# AWR2243_DUT.net
KiCad netlist of a schematic drawn in Altium Designer
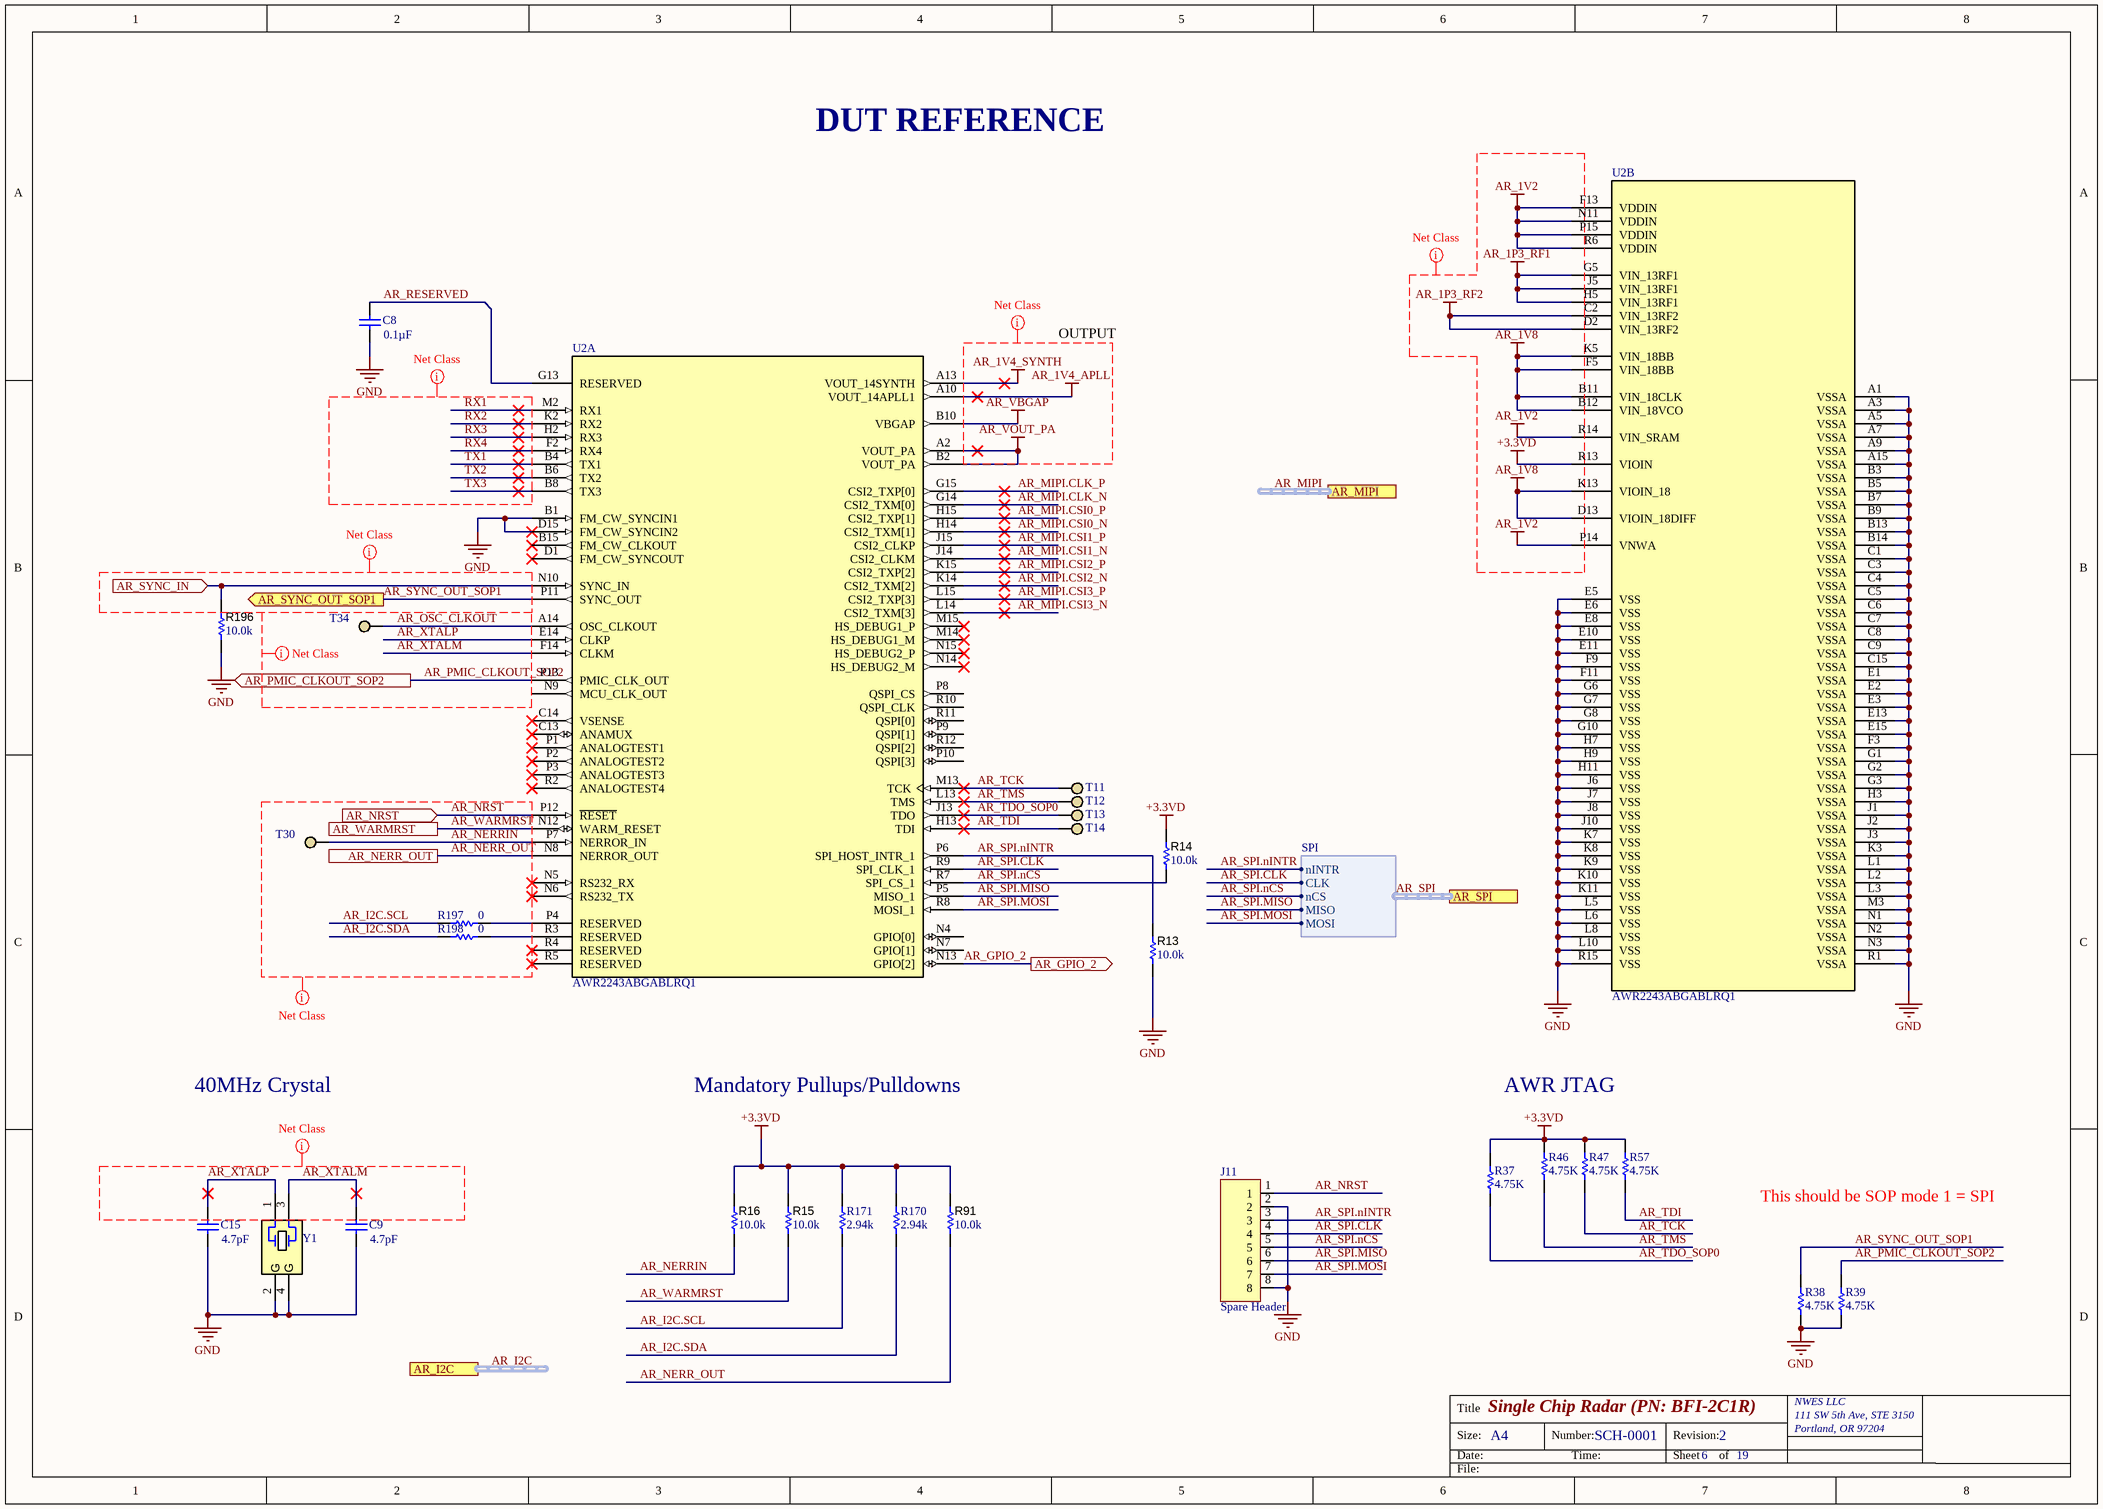
[diagram p0: AWR2243_DUT.SchDoc]

(export (version "E")
  (design (tool "Eeschema 10.0.6"))
  (components
    (comp (ref "C8")
      (value "C0603X7S1A104K030BC")
      (footprint "0201_033")
      (description "CAP, CERM, 0.1 µF, 10 V,+/- 10%, X7S, 0201")
      (fields (field (name "MANUFACTURER") "TDK") (field (name "VALUEDISPLAYED") "0.1µF"))
      (libsource (lib "Altium Vault - TI") (part "Capacitor"))
    )
    (comp (ref "C9")
      (value "GJM1555C1H4R7BB01D")
      (footprint "0402")
      (description "CAP, CERM, 4.7 pF, 50 V, +/- 2%, C0G/NP0, 0402")
      (fields
        (field (name "MANUFACTURER") "MuRata")
        (field (name "VALUEDISPLAYED") "4.7pF")
        (field (name "PUBLISHER") "Texas Instruments")
      )
      (libsource (lib "Altium Vault - TI") (part "CMP-0006367-2"))
    )
    (comp (ref "C15")
      (value "GJM1555C1H4R7BB01D")
      (footprint "0402")
      (description "CAP, CERM, 4.7 pF, 50 V, +/- 2%, C0G/NP0, 0402")
      (fields
        (field (name "MANUFACTURER") "MuRata")
        (field (name "VALUEDISPLAYED") "4.7pF")
        (field (name "PUBLISHER") "Texas Instruments")
      )
      (libsource (lib "Altium Vault - TI") (part "CMP-0006367-2"))
    )
    (comp (ref "J11")
      (value "Spare Header")
      (footprint "HDR8X1_2.54MM")
      (description "Conn Header Vert 8POS 2.54MM")
      (fields
        (field (name "MANUFACTURER") "Sullins")
        (field (name "MANUFACTURER PART NUMBER") "PREC008SAAN-RC")
      )
      (libsource (lib "Radar FPGA RF") (part "Header 8X1"))
    )
    (comp (ref "R13")
      (value "CRCW040210K0FKED")
      (footprint "0402L")
      (description "RES, 10.0 k, 1%, 0.063 W, AEC-Q200 Grade 0, 0402")
      (fields (field (name "MANUFACTURER") "Vishay-Dale") (field (name "VALUEDISPLAYED") "10.0k"))
      (libsource (lib "Altium Vault - TI") (part "Resistor"))
    )
    (comp (ref "R14")
      (value "CRCW040210K0FKED")
      (footprint "0402L")
      (description "RES, 10.0 k, 1%, 0.063 W, AEC-Q200 Grade 0, 0402")
      (fields (field (name "MANUFACTURER") "Vishay-Dale") (field (name "VALUEDISPLAYED") "10.0k"))
      (libsource (lib "Altium Vault - TI") (part "Resistor"))
    )
    (comp (ref "R15")
      (value "CRCW040210K0FKED")
      (footprint "0402L")
      (description "RES, 10.0 k, 1%, 0.063 W, AEC-Q200 Grade 0, 0402")
      (fields (field (name "MANUFACTURER") "Vishay-Dale") (field (name "VALUEDISPLAYED") "10.0k"))
      (libsource (lib "Altium Vault - TI") (part "Resistor"))
    )
    (comp (ref "R16")
      (value "CRCW040210K0FKED")
      (footprint "0402L")
      (description "RES, 10.0 k, 1%, 0.063 W, AEC-Q200 Grade 0, 0402")
      (fields (field (name "MANUFACTURER") "Vishay-Dale") (field (name "VALUEDISPLAYED") "10.0k"))
      (libsource (lib "Altium Vault - TI") (part "Resistor"))
    )
    (comp (ref "R37")
      (value "4.75K")
      (footprint "RESC1005X40USR")
      (description "RES 4.75K OHM 1% 1/16W 0402")
      (fields
        (field (name "MANUFACTURER") "YAGEO")
        (field (name "MANUFACTURER PART NUMBER") "RC0402FR-074K75L")
      )
      (libsource (lib "Radar FPGA RF") (part "RES 4.75K OHM 1% 1/16W 0402"))
    )
    (comp (ref "R38")
      (value "4.75K")
      (footprint "RESC1005X40USR")
      (description "RES 4.75K OHM 1% 1/16W 0402")
      (fields
        (field (name "MANUFACTURER") "YAGEO")
        (field (name "MANUFACTURER PART NUMBER") "RC0402FR-074K75L")
      )
      (libsource (lib "Radar FPGA RF") (part "RES 4.75K OHM 1% 1/16W 0402"))
    )
    (comp (ref "R39")
      (value "4.75K")
      (footprint "RESC1005X40USR")
      (description "RES 4.75K OHM 1% 1/16W 0402")
      (fields
        (field (name "MANUFACTURER") "YAGEO")
        (field (name "MANUFACTURER PART NUMBER") "RC0402FR-074K75L")
      )
      (libsource (lib "Radar FPGA RF") (part "RES 4.75K OHM 1% 1/16W 0402"))
    )
    (comp (ref "R46")
      (value "4.75K")
      (footprint "RESC1005X40USR")
      (description "RES 4.75K OHM 1% 1/16W 0402")
      (fields
        (field (name "MANUFACTURER") "YAGEO")
        (field (name "MANUFACTURER PART NUMBER") "RC0402FR-074K75L")
      )
      (libsource (lib "Radar FPGA RF") (part "RES 4.75K OHM 1% 1/16W 0402"))
    )
    (comp (ref "R47")
      (value "4.75K")
      (footprint "RESC1005X40USR")
      (description "RES 4.75K OHM 1% 1/16W 0402")
      (fields
        (field (name "MANUFACTURER") "YAGEO")
        (field (name "MANUFACTURER PART NUMBER") "RC0402FR-074K75L")
      )
      (libsource (lib "Radar FPGA RF") (part "RES 4.75K OHM 1% 1/16W 0402"))
    )
    (comp (ref "R57")
      (value "4.75K")
      (footprint "RESC1005X40USR")
      (description "RES 4.75K OHM 1% 1/16W 0402")
      (fields
        (field (name "MANUFACTURER") "YAGEO")
        (field (name "MANUFACTURER PART NUMBER") "RC0402FR-074K75L")
      )
      (libsource (lib "Radar FPGA RF") (part "RES 4.75K OHM 1% 1/16W 0402"))
    )
    (comp (ref "R91")
      (value "CRCW040210K0FKED")
      (footprint "0402L")
      (description "RES, 10.0 k, 1%, 0.063 W, AEC-Q200 Grade 0, 0402")
      (fields (field (name "MANUFACTURER") "Vishay-Dale") (field (name "VALUEDISPLAYED") "10.0k"))
      (libsource (lib "Altium Vault - TI") (part "Resistor"))
    )
    (comp (ref "R170")
      (value "CRCW04022K94FKED")
      (footprint "0402")
      (description "RES, 2.94 k, 1%, 0.063 W, AEC-Q200 Grade 0, 0402")
      (fields (field (name "MANUFACTURER") "Vishay-Dale") (field (name "VALUEDISPLAYED") "2.94k"))
      (libsource (lib "Altium Vault - TI") (part "Resistor"))
    )
    (comp (ref "R171")
      (value "CRCW04022K94FKED")
      (footprint "0402")
      (description "RES, 2.94 k, 1%, 0.063 W, AEC-Q200 Grade 0, 0402")
      (fields (field (name "MANUFACTURER") "Vishay-Dale") (field (name "VALUEDISPLAYED") "2.94k"))
      (libsource (lib "Altium Vault - TI") (part "Resistor"))
    )
    (comp (ref "R196")
      (value "CRCW040210K0FKED")
      (footprint "0402L")
      (description "RES, 10.0 k, 1%, 0.063 W, AEC-Q200 Grade 0, 0402")
      (fields (field (name "MANUFACTURER") "Vishay-Dale") (field (name "VALUEDISPLAYED") "10.0k"))
      (libsource (lib "Altium Vault - TI") (part "CMP-0025958-3"))
    )
    (comp (ref "R197")
      (value "CRCW02010000Z0ED")
      (footprint "0201")
      (description "RES, 0, 5%, 0.05 W, 0201")
      (fields (field (name "MANUFACTURER") "Vishay-Dale") (field (name "VALUEDISPLAYED") "0"))
      (libsource (lib "Altium Vault - TI") (part "Resistor"))
    )
    (comp (ref "R198")
      (value "CRCW02010000Z0ED")
      (footprint "0201")
      (description "RES, 0, 5%, 0.05 W, 0201")
      (fields (field (name "MANUFACTURER") "Vishay-Dale") (field (name "VALUEDISPLAYED") "0"))
      (libsource (lib "Altium Vault - TI") (part "Resistor"))
    )
    (comp (ref "T11")
      (value "TP_S")
      (footprint "TP_SM_1MM")
      (description "test point")
      (libsource (lib "Radar FPGA RF") (part "Test point PAD"))
    )
    (comp (ref "T12")
      (value "TP_S")
      (footprint "TP_SM_1MM")
      (description "test point")
      (libsource (lib "Radar FPGA RF") (part "Test point PAD"))
    )
    (comp (ref "T13")
      (value "TP_S")
      (footprint "TP_SM_1MM")
      (description "test point")
      (libsource (lib "Radar FPGA RF") (part "Test point PAD"))
    )
    (comp (ref "T14")
      (value "TP_S")
      (footprint "TP_SM_1MM")
      (description "test point")
      (libsource (lib "Radar FPGA RF") (part "Test point PAD"))
    )
    (comp (ref "T30")
      (value "TP_S")
      (footprint "TP_SM_1MM")
      (description "test point")
      (libsource (lib "Radar FPGA RF") (part "Test point PAD"))
    )
    (comp (ref "T34")
      (value "TP_S")
      (footprint "TP_SM_1MM")
      (description "test point")
      (libsource (lib "Radar FPGA RF") (part "Test point PAD"))
    )
    (comp (ref "U2")
      (value "AWR2243APBGABLQ1")
      (footprint "ABL0161A")
      (description "Single Chip 77 and 79 GHz FMCW Transceiver, ABL0161A (FCBGA-161)")
      (fields
        (field (name "ALTERNATE PARTNUMBER") "AWR2243ABGABLRQ1")
        (field (name "MANUFACTURER") "Texas Instruments")
        (field (name "PARTNUMBER") "AWR2243ABGABLRQ1")
      )
      (libsource (lib "Altium Vault - TI") (part "CMP-0081285-1"))
    )
    (comp (ref "Y1")
      (value "CX3225SA40000D0PTWCC")
      (footprint "Kyocera_CX3225SA")
      (description "Crystal, 40 MHz, 8pF, SMD")
      (fields (field (name "MANUFACTURER") "Kyocera"))
      (libsource (lib "Altium Vault - TI") (part "XTAL_4P_13_24OPEN"))
    )
  )
  (nets
    (net (code "4") (name "+3.3VD") (class "Default")
      (node (ref "R14") (pin "2") (pinfunction "2_2") (pintype "passive"))
      (node (ref "R15") (pin "2") (pinfunction "2_2") (pintype "passive"))
      (node (ref "R16") (pin "2") (pinfunction "2_2") (pintype "passive"))
      (node (ref "R170") (pin "2") (pinfunction "2_2") (pintype "passive"))
      (node (ref "R171") (pin "2") (pinfunction "2_2") (pintype "passive"))
      (node (ref "R37") (pin "2") (pinfunction "2_2") (pintype "passive"))
      (node (ref "R46") (pin "2") (pinfunction "2_2") (pintype "passive"))
      (node (ref "R47") (pin "2") (pinfunction "2_2") (pintype "passive"))
      (node (ref "R57") (pin "2") (pinfunction "2_2") (pintype "passive"))
      (node (ref "R91") (pin "2") (pinfunction "2_2") (pintype "passive"))
      (node (ref "U2") (pin "R13") (pinfunction "VIOIN_R13") (pintype "power_in"))
    )
    (net (code "5") (name "/AR_GPIO_2") (class "Default")
      (node (ref "U2") (pin "N13") (pinfunction "GPIO[2]_N13") (pintype "bidirectional"))
    )
    (net (code "6") (name "/AR_I2C.SCL") (class "Default")
      (node (ref "R171") (pin "1") (pinfunction "1_1") (pintype "passive"))
      (node (ref "R197") (pin "1") (pinfunction "1_1") (pintype "passive"))
    )
    (net (code "7") (name "/AR_I2C.SDA") (class "Default")
      (node (ref "R170") (pin "1") (pinfunction "1_1") (pintype "passive"))
      (node (ref "R198") (pin "1") (pinfunction "1_1") (pintype "passive"))
    )
    (net (code "8") (name "/AR_MIPI.CLK_N") (class "Default")
      (node (ref "U2") (pin "G14") (pinfunction "CSI2_TXM[0]_G14") (pintype "output"))
    )
    (net (code "9") (name "/AR_MIPI.CLK_P") (class "Default")
      (node (ref "U2") (pin "G15") (pinfunction "CSI2_TXP[0]_G15") (pintype "output"))
    )
    (net (code "10") (name "/AR_MIPI.CSI0_N") (class "Default")
      (node (ref "U2") (pin "H14") (pinfunction "CSI2_TXM[1]_H14") (pintype "output"))
    )
    (net (code "11") (name "/AR_MIPI.CSI0_P") (class "Default")
      (node (ref "U2") (pin "H15") (pinfunction "CSI2_TXP[1]_H15") (pintype "output"))
    )
    (net (code "12") (name "/AR_MIPI.CSI1_N") (class "Default")
      (node (ref "U2") (pin "J14") (pinfunction "CSI2_CLKM_J14") (pintype "output"))
    )
    (net (code "13") (name "/AR_MIPI.CSI1_P") (class "Default")
      (node (ref "U2") (pin "J15") (pinfunction "CSI2_CLKP_J15") (pintype "output"))
    )
    (net (code "14") (name "/AR_MIPI.CSI2_N") (class "Default")
      (node (ref "U2") (pin "K14") (pinfunction "CSI2_TXM[2]_K14") (pintype "output"))
    )
    (net (code "15") (name "/AR_MIPI.CSI2_P") (class "Default")
      (node (ref "U2") (pin "K15") (pinfunction "CSI2_TXP[2]_K15") (pintype "output"))
    )
    (net (code "16") (name "/AR_MIPI.CSI3_N") (class "Default")
      (node (ref "U2") (pin "L14") (pinfunction "CSI2_TXM[3]_L14") (pintype "output"))
    )
    (net (code "17") (name "/AR_MIPI.CSI3_P") (class "Default")
      (node (ref "U2") (pin "L15") (pinfunction "CSI2_TXP[3]_L15") (pintype "output"))
    )
    (net (code "18") (name "/AR_NERRIN") (class "Default")
      (node (ref "R16") (pin "1") (pinfunction "1_1") (pintype "passive"))
      (node (ref "T30") (pin "1") (pintype "passive"))
      (node (ref "U2") (pin "P7") (pinfunction "NERROR_IN_P7") (pintype "input"))
    )
    (net (code "19") (name "/AR_NERR_OUT") (class "Default")
      (node (ref "R91") (pin "1") (pinfunction "1_1") (pintype "passive"))
      (node (ref "U2") (pin "N8") (pinfunction "NERROR_OUT_N8") (pintype "open_collector"))
    )
    (net (code "20") (name "/AR_NRST") (class "Default")
      (node (ref "J11") (pin "1") (pinfunction "1_1") (pintype "passive"))
      (node (ref "U2") (pin "P12") (pinfunction "RESET_P12") (pintype "input"))
    )
    (net (code "21") (name "/AR_OSC_CLKOUT") (class "Default")
      (node (ref "T34") (pin "1") (pintype "passive"))
      (node (ref "U2") (pin "A14") (pinfunction "OSC_CLKOUT_A14") (pintype "output"))
    )
    (net (code "22") (name "/AR_PMIC_CLKOUT_SOP2") (class "Default")
      (node (ref "R39") (pin "2") (pinfunction "2_2") (pintype "passive"))
      (node (ref "U2") (pin "P13") (pinfunction "PMIC_CLK_OUT_P13") (pintype "output"))
    )
    (net (code "23") (name "/AR_RESERVED") (class "Default")
      (node (ref "C8") (pin "1") (pinfunction "1_1") (pintype "passive"))
      (node (ref "U2") (pin "G13") (pinfunction "RESERVED_G13") (pintype "power_in"))
    )
    (net (code "24") (name "/AR_SPI.CLK") (class "Default")
      (node (ref "J11") (pin "4") (pinfunction "4_4") (pintype "passive"))
      (node (ref "U2") (pin "R9") (pinfunction "SPI_CLK_1_R9") (pintype "input"))
    )
    (net (code "25") (name "/AR_SPI.MISO") (class "Default")
      (node (ref "J11") (pin "6") (pinfunction "6_6") (pintype "passive"))
      (node (ref "U2") (pin "P5") (pinfunction "MISO_1_P5") (pintype "output"))
    )
    (net (code "26") (name "/AR_SPI.MOSI") (class "Default")
      (node (ref "J11") (pin "7") (pinfunction "7_7") (pintype "passive"))
      (node (ref "U2") (pin "R8") (pinfunction "MOSI_1_R8") (pintype "input"))
    )
    (net (code "27") (name "/AR_SPI.nCS") (class "Default")
      (node (ref "J11") (pin "5") (pinfunction "5_5") (pintype "passive"))
      (node (ref "R14") (pin "1") (pinfunction "1_1") (pintype "passive"))
      (node (ref "U2") (pin "R7") (pinfunction "SPI_CS_1_R7") (pintype "input"))
    )
    (net (code "28") (name "/AR_SPI.nINTR") (class "Default")
      (node (ref "J11") (pin "3") (pinfunction "3_3") (pintype "passive"))
      (node (ref "R13") (pin "2") (pinfunction "2_2") (pintype "passive"))
      (node (ref "U2") (pin "P6") (pinfunction "SPI_HOST_INTR_1_P6") (pintype "output"))
    )
    (net (code "30") (name "/AR_SYNC_IN") (class "Default")
      (node (ref "R196") (pin "2") (pinfunction "2_2") (pintype "passive"))
      (node (ref "U2") (pin "N10") (pinfunction "SYNC_IN_N10") (pintype "input"))
    )
    (net (code "31") (name "/AR_SYNC_OUT_SOP1") (class "Default")
      (node (ref "R38") (pin "2") (pinfunction "2_2") (pintype "passive"))
      (node (ref "U2") (pin "P11") (pinfunction "SYNC_OUT_P11") (pintype "output"))
    )
    (net (code "32") (name "/AR_TCK") (class "Default")
      (node (ref "R47") (pin "1") (pinfunction "1_1") (pintype "passive"))
      (node (ref "T11") (pin "1") (pintype "passive"))
      (node (ref "U2") (pin "M13") (pinfunction "TCK_M13") (pintype "input"))
    )
    (net (code "33") (name "/AR_TDI") (class "Default")
      (node (ref "R57") (pin "1") (pinfunction "1_1") (pintype "passive"))
      (node (ref "T14") (pin "1") (pintype "passive"))
      (node (ref "U2") (pin "H13") (pinfunction "TDI_H13") (pintype "input"))
    )
    (net (code "34") (name "/AR_TDO_SOP0") (class "Default")
      (node (ref "R37") (pin "1") (pinfunction "1_1") (pintype "passive"))
      (node (ref "T13") (pin "1") (pintype "passive"))
      (node (ref "U2") (pin "J13") (pinfunction "TDO_J13") (pintype "output"))
    )
    (net (code "35") (name "/AR_TMS") (class "Default")
      (node (ref "R46") (pin "1") (pinfunction "1_1") (pintype "passive"))
      (node (ref "T12") (pin "1") (pintype "passive"))
      (node (ref "U2") (pin "L13") (pinfunction "TMS_L13") (pintype "input"))
    )
    (net (code "36") (name "/AR_WARMRST") (class "Default")
      (node (ref "R15") (pin "1") (pinfunction "1_1") (pintype "passive"))
      (node (ref "U2") (pin "N12") (pinfunction "WARM_RESET_N12") (pintype "bidirectional"))
    )
    (net (code "37") (name "/AR_XTALM") (class "Default")
      (node (ref "C9") (pin "1") (pinfunction "1_1") (pintype "passive"))
      (node (ref "U2") (pin "F14") (pinfunction "CLKM_F14") (pintype "input"))
      (node (ref "Y1") (pin "3") (pinfunction "3_3") (pintype "passive"))
    )
    (net (code "38") (name "/AR_XTALP") (class "Default")
      (node (ref "C15") (pin "2") (pinfunction "2_2") (pintype "passive"))
      (node (ref "U2") (pin "E14") (pinfunction "CLKP_E14") (pintype "input"))
      (node (ref "Y1") (pin "1") (pinfunction "1_1") (pintype "passive"))
    )
    (net (code "39") (name "/RX1") (class "Default")
      (node (ref "U2") (pin "M2") (pinfunction "RX1_M2") (pintype "input"))
    )
    (net (code "40") (name "/RX2") (class "Default")
      (node (ref "U2") (pin "K2") (pinfunction "RX2_K2") (pintype "input"))
    )
    (net (code "41") (name "/RX3") (class "Default")
      (node (ref "U2") (pin "H2") (pinfunction "RX3_H2") (pintype "input"))
    )
    (net (code "42") (name "/RX4") (class "Default")
      (node (ref "U2") (pin "F2") (pinfunction "RX4_F2") (pintype "input"))
    )
    (net (code "43") (name "/TX1") (class "Default")
      (node (ref "U2") (pin "B4") (pinfunction "TX1_B4") (pintype "output"))
    )
    (net (code "44") (name "/TX2") (class "Default")
      (node (ref "U2") (pin "B6") (pinfunction "TX2_B6") (pintype "output"))
    )
    (net (code "45") (name "/TX3") (class "Default")
      (node (ref "U2") (pin "B8") (pinfunction "TX3_B8") (pintype "output"))
    )
    (net (code "48") (name "AR_1P3_RF1") (class "Default")
      (node (ref "U2") (pin "G5") (pinfunction "VIN_13RF1_G5") (pintype "power_in"))
      (node (ref "U2") (pin "H5") (pinfunction "VIN_13RF1_H5") (pintype "power_in"))
      (node (ref "U2") (pin "J5") (pinfunction "VIN_13RF1_J5") (pintype "power_in"))
    )
    (net (code "49") (name "AR_1P3_RF2") (class "Default")
      (node (ref "U2") (pin "C2") (pinfunction "VIN_13RF2_C2") (pintype "power_in"))
      (node (ref "U2") (pin "D2") (pinfunction "VIN_13RF2_D2") (pintype "power_in"))
    )
    (net (code "50") (name "AR_1V2") (class "Default")
      (node (ref "U2") (pin "F13") (pinfunction "VDDIN_F13") (pintype "power_in"))
      (node (ref "U2") (pin "N11") (pinfunction "VDDIN_N11") (pintype "power_in"))
      (node (ref "U2") (pin "P14") (pinfunction "VNWA_P14") (pintype "power_in"))
      (node (ref "U2") (pin "P15") (pinfunction "VDDIN_P15") (pintype "power_in"))
      (node (ref "U2") (pin "R14") (pinfunction "VIN_SRAM_R14") (pintype "power_in"))
      (node (ref "U2") (pin "R6") (pinfunction "VDDIN_R6") (pintype "power_in"))
    )
    (net (code "51") (name "AR_1V4_APLL") (class "Default")
      (node (ref "U2") (pin "A10") (pinfunction "VOUT_14APLL1_A10") (pintype "output"))
    )
    (net (code "52") (name "AR_1V4_SYNTH") (class "Default")
      (node (ref "U2") (pin "A13") (pinfunction "VOUT_14SYNTH_A13") (pintype "output"))
    )
    (net (code "53") (name "AR_1V8") (class "Default")
      (node (ref "U2") (pin "B11") (pinfunction "VIN_18CLK_B11") (pintype "power_in"))
      (node (ref "U2") (pin "B12") (pinfunction "VIN_18VCO_B12") (pintype "power_in"))
      (node (ref "U2") (pin "D13") (pinfunction "VIOIN_18DIFF_D13") (pintype "power_in"))
      (node (ref "U2") (pin "F5") (pinfunction "VIN_18BB_F5") (pintype "power_in"))
      (node (ref "U2") (pin "K13") (pinfunction "VIOIN_18_K13") (pintype "power_in"))
      (node (ref "U2") (pin "K5") (pinfunction "VIN_18BB_K5") (pintype "power_in"))
    )
    (net (code "54") (name "AR_VBGAP") (class "Default")
      (node (ref "U2") (pin "B10") (pinfunction "VBGAP_B10") (pintype "output"))
    )
    (net (code "55") (name "AR_VOUT_PA") (class "Default")
      (node (ref "U2") (pin "A2") (pinfunction "VOUT_PA_A2") (pintype "output"))
      (node (ref "U2") (pin "B2") (pinfunction "VOUT_PA_B2") (pintype "output"))
    )
    (net (code "56") (name "GND") (class "Default")
      (node (ref "C15") (pin "1") (pinfunction "1_1") (pintype "passive"))
      (node (ref "C8") (pin "2") (pinfunction "2_2") (pintype "passive"))
      (node (ref "C9") (pin "2") (pinfunction "2_2") (pintype "passive"))
      (node (ref "J11") (pin "2") (pinfunction "2_2") (pintype "passive"))
      (node (ref "J11") (pin "8") (pinfunction "8_8") (pintype "passive"))
      (node (ref "R13") (pin "1") (pinfunction "1_1") (pintype "passive"))
      (node (ref "R196") (pin "1") (pinfunction "1_1") (pintype "passive"))
      (node (ref "R38") (pin "1") (pinfunction "1_1") (pintype "passive"))
      (node (ref "R39") (pin "1") (pinfunction "1_1") (pintype "passive"))
      (node (ref "U2") (pin "A1") (pinfunction "VSSA_A1") (pintype "power_in"))
      (node (ref "U2") (pin "A15") (pinfunction "VSSA_A15") (pintype "power_in"))
      (node (ref "U2") (pin "A3") (pinfunction "VSSA_A3") (pintype "power_in"))
      (node (ref "U2") (pin "A5") (pinfunction "VSSA_A5") (pintype "power_in"))
      (node (ref "U2") (pin "A7") (pinfunction "VSSA_A7") (pintype "power_in"))
      (node (ref "U2") (pin "A9") (pinfunction "VSSA_A9") (pintype "power_in"))
      (node (ref "U2") (pin "B1") (pinfunction "FM_CW_SYNCIN1_B1") (pintype "input"))
      (node (ref "U2") (pin "B13") (pinfunction "VSSA_B13") (pintype "power_in"))
      (node (ref "U2") (pin "B14") (pinfunction "VSSA_B14") (pintype "power_in"))
      (node (ref "U2") (pin "B3") (pinfunction "VSSA_B3") (pintype "power_in"))
      (node (ref "U2") (pin "B5") (pinfunction "VSSA_B5") (pintype "power_in"))
      (node (ref "U2") (pin "B7") (pinfunction "VSSA_B7") (pintype "power_in"))
      (node (ref "U2") (pin "B9") (pinfunction "VSSA_B9") (pintype "power_in"))
      (node (ref "U2") (pin "C1") (pinfunction "VSSA_C1") (pintype "power_in"))
      (node (ref "U2") (pin "C15") (pinfunction "VSSA_C15") (pintype "power_in"))
      (node (ref "U2") (pin "C3") (pinfunction "VSSA_C3") (pintype "power_in"))
      (node (ref "U2") (pin "C4") (pinfunction "VSSA_C4") (pintype "power_in"))
      (node (ref "U2") (pin "C5") (pinfunction "VSSA_C5") (pintype "power_in"))
      (node (ref "U2") (pin "C6") (pinfunction "VSSA_C6") (pintype "power_in"))
      (node (ref "U2") (pin "C7") (pinfunction "VSSA_C7") (pintype "power_in"))
      (node (ref "U2") (pin "C8") (pinfunction "VSSA_C8") (pintype "power_in"))
      (node (ref "U2") (pin "C9") (pinfunction "VSSA_C9") (pintype "power_in"))
      (node (ref "U2") (pin "D15") (pinfunction "FM_CW_SYNCIN2_D15") (pintype "input"))
      (node (ref "U2") (pin "E1") (pinfunction "VSSA_E1") (pintype "power_in"))
      (node (ref "U2") (pin "E10") (pinfunction "VSS_E10") (pintype "power_in"))
      (node (ref "U2") (pin "E11") (pinfunction "VSS_E11") (pintype "power_in"))
      (node (ref "U2") (pin "E13") (pinfunction "VSSA_E13") (pintype "power_in"))
      (node (ref "U2") (pin "E15") (pinfunction "VSSA_E15") (pintype "power_in"))
      (node (ref "U2") (pin "E2") (pinfunction "VSSA_E2") (pintype "power_in"))
      (node (ref "U2") (pin "E3") (pinfunction "VSSA_E3") (pintype "power_in"))
      (node (ref "U2") (pin "E5") (pinfunction "VSS_E5") (pintype "power_in"))
      (node (ref "U2") (pin "E6") (pinfunction "VSS_E6") (pintype "power_in"))
      (node (ref "U2") (pin "E8") (pinfunction "VSS_E8") (pintype "power_in"))
      (node (ref "U2") (pin "F11") (pinfunction "VSS_F11") (pintype "power_in"))
      (node (ref "U2") (pin "F3") (pinfunction "VSSA_F3") (pintype "power_in"))
      (node (ref "U2") (pin "F9") (pinfunction "VSS_F9") (pintype "power_in"))
      (node (ref "U2") (pin "G1") (pinfunction "VSSA_G1") (pintype "power_in"))
      (node (ref "U2") (pin "G10") (pinfunction "VSS_G10") (pintype "power_in"))
      (node (ref "U2") (pin "G2") (pinfunction "VSSA_G2") (pintype "power_in"))
      (node (ref "U2") (pin "G3") (pinfunction "VSSA_G3") (pintype "power_in"))
      (node (ref "U2") (pin "G6") (pinfunction "VSS_G6") (pintype "power_in"))
      (node (ref "U2") (pin "G7") (pinfunction "VSS_G7") (pintype "power_in"))
      (node (ref "U2") (pin "G8") (pinfunction "VSS_G8") (pintype "power_in"))
      (node (ref "U2") (pin "H11") (pinfunction "VSS_H11") (pintype "power_in"))
      (node (ref "U2") (pin "H3") (pinfunction "VSSA_H3") (pintype "power_in"))
      (node (ref "U2") (pin "H7") (pinfunction "VSS_H7") (pintype "power_in"))
      (node (ref "U2") (pin "H9") (pinfunction "VSS_H9") (pintype "power_in"))
      (node (ref "U2") (pin "J1") (pinfunction "VSSA_J1") (pintype "power_in"))
      (node (ref "U2") (pin "J10") (pinfunction "VSS_J10") (pintype "power_in"))
      (node (ref "U2") (pin "J2") (pinfunction "VSSA_J2") (pintype "power_in"))
      (node (ref "U2") (pin "J3") (pinfunction "VSSA_J3") (pintype "power_in"))
      (node (ref "U2") (pin "J6") (pinfunction "VSS_J6") (pintype "power_in"))
      (node (ref "U2") (pin "J7") (pinfunction "VSS_J7") (pintype "power_in"))
      (node (ref "U2") (pin "J8") (pinfunction "VSS_J8") (pintype "power_in"))
      (node (ref "U2") (pin "K10") (pinfunction "VSS_K10") (pintype "power_in"))
      (node (ref "U2") (pin "K11") (pinfunction "VSS_K11") (pintype "power_in"))
      (node (ref "U2") (pin "K3") (pinfunction "VSSA_K3") (pintype "power_in"))
      (node (ref "U2") (pin "K7") (pinfunction "VSS_K7") (pintype "power_in"))
      (node (ref "U2") (pin "K8") (pinfunction "VSS_K8") (pintype "power_in"))
      (node (ref "U2") (pin "K9") (pinfunction "VSS_K9") (pintype "power_in"))
      (node (ref "U2") (pin "L1") (pinfunction "VSSA_L1") (pintype "power_in"))
      (node (ref "U2") (pin "L10") (pinfunction "VSS_L10") (pintype "power_in"))
      (node (ref "U2") (pin "L2") (pinfunction "VSSA_L2") (pintype "power_in"))
      (node (ref "U2") (pin "L3") (pinfunction "VSSA_L3") (pintype "power_in"))
      (node (ref "U2") (pin "L5") (pinfunction "VSS_L5") (pintype "power_in"))
      (node (ref "U2") (pin "L6") (pinfunction "VSS_L6") (pintype "power_in"))
      (node (ref "U2") (pin "L8") (pinfunction "VSS_L8") (pintype "power_in"))
      (node (ref "U2") (pin "M3") (pinfunction "VSSA_M3") (pintype "power_in"))
      (node (ref "U2") (pin "N1") (pinfunction "VSSA_N1") (pintype "power_in"))
      (node (ref "U2") (pin "N2") (pinfunction "VSSA_N2") (pintype "power_in"))
      (node (ref "U2") (pin "N3") (pinfunction "VSSA_N3") (pintype "power_in"))
      (node (ref "U2") (pin "R1") (pinfunction "VSSA_R1") (pintype "power_in"))
      (node (ref "U2") (pin "R15") (pinfunction "VSS_R15") (pintype "power_in"))
      (node (ref "Y1") (pin "2") (pinfunction "GND_2") (pintype "power_in"))
      (node (ref "Y1") (pin "4") (pinfunction "GND_4") (pintype "power_in"))
    )
    (net (code "57") (name "Net-(R197-Pad2)") (class "Default")
      (node (ref "R197") (pin "2") (pinfunction "2_2") (pintype "passive"))
      (node (ref "U2") (pin "P4") (pinfunction "RESERVED_P4") (pintype "passive"))
    )
    (net (code "58") (name "Net-(R198-Pad2)") (class "Default")
      (node (ref "R198") (pin "2") (pinfunction "2_2") (pintype "passive"))
      (node (ref "U2") (pin "R3") (pinfunction "RESERVED_R3") (pintype "passive"))
    )
    (net (code "59") (name "unconnected-(U2A-ANALOGTEST1-PadP1)") (class "Default")
      (node (ref "U2") (pin "P1") (pinfunction "ANALOGTEST1_P1") (pintype "output+no_connect"))
    )
    (net (code "60") (name "unconnected-(U2A-ANALOGTEST2-PadP2)") (class "Default")
      (node (ref "U2") (pin "P2") (pinfunction "ANALOGTEST2_P2") (pintype "output+no_connect"))
    )
    (net (code "61") (name "unconnected-(U2A-ANALOGTEST3-PadP3)") (class "Default")
      (node (ref "U2") (pin "P3") (pinfunction "ANALOGTEST3_P3") (pintype "output+no_connect"))
    )
    (net (code "62") (name "unconnected-(U2A-ANALOGTEST4-PadR2)") (class "Default")
      (node (ref "U2") (pin "R2") (pinfunction "ANALOGTEST4_R2") (pintype "output+no_connect"))
    )
    (net (code "63") (name "unconnected-(U2A-ANAMUX-PadC13)") (class "Default")
      (node (ref "U2") (pin "C13") (pinfunction "ANAMUX_C13") (pintype "bidirectional+no_connect"))
    )
    (net (code "64") (name "unconnected-(U2A-FM_CW_CLKOUT-PadB15)") (class "Default")
      (node (ref "U2") (pin "B15") (pinfunction "FM_CW_CLKOUT_B15") (pintype "output+no_connect"))
    )
    (net (code "65") (name "unconnected-(U2A-FM_CW_SYNCOUT-PadD1)") (class "Default")
      (node (ref "U2") (pin "D1") (pinfunction "FM_CW_SYNCOUT_D1") (pintype "output+no_connect"))
    )
    (net (code "66") (name "unconnected-(U2A-GPIO[0]-PadN4)") (class "Default")
      (node (ref "U2") (pin "N4") (pinfunction "GPIO[0]_N4") (pintype "bidirectional"))
    )
    (net (code "67") (name "unconnected-(U2A-GPIO[1]-PadN7)") (class "Default")
      (node (ref "U2") (pin "N7") (pinfunction "GPIO[1]_N7") (pintype "bidirectional"))
    )
    (net (code "68") (name "unconnected-(U2A-HS_DEBUG1_M-PadM14)") (class "Default")
      (node (ref "U2") (pin "M14") (pinfunction "HS_DEBUG1_M_M14") (pintype "output+no_connect"))
    )
    (net (code "69") (name "unconnected-(U2A-HS_DEBUG1_P-PadM15)") (class "Default")
      (node (ref "U2") (pin "M15") (pinfunction "HS_DEBUG1_P_M15") (pintype "output+no_connect"))
    )
    (net (code "70") (name "unconnected-(U2A-HS_DEBUG2_M-PadN14)") (class "Default")
      (node (ref "U2") (pin "N14") (pinfunction "HS_DEBUG2_M_N14") (pintype "output+no_connect"))
    )
    (net (code "71") (name "unconnected-(U2A-HS_DEBUG2_P-PadN15)") (class "Default")
      (node (ref "U2") (pin "N15") (pinfunction "HS_DEBUG2_P_N15") (pintype "output+no_connect"))
    )
    (net (code "72") (name "unconnected-(U2A-MCU_CLK_OUT-PadN9)") (class "Default")
      (node (ref "U2") (pin "N9") (pinfunction "MCU_CLK_OUT_N9") (pintype "output"))
    )
    (net (code "73") (name "unconnected-(U2A-QSPI[0]-PadR11)") (class "Default")
      (node (ref "U2") (pin "R11") (pinfunction "QSPI[0]_R11") (pintype "bidirectional"))
    )
    (net (code "74") (name "unconnected-(U2A-QSPI[1]-PadP9)") (class "Default")
      (node (ref "U2") (pin "P9") (pinfunction "QSPI[1]_P9") (pintype "bidirectional"))
    )
    (net (code "75") (name "unconnected-(U2A-QSPI[2]-PadR12)") (class "Default")
      (node (ref "U2") (pin "R12") (pinfunction "QSPI[2]_R12") (pintype "bidirectional"))
    )
    (net (code "76") (name "unconnected-(U2A-QSPI[3]-PadP10)") (class "Default")
      (node (ref "U2") (pin "P10") (pinfunction "QSPI[3]_P10") (pintype "bidirectional"))
    )
    (net (code "77") (name "unconnected-(U2A-QSPI_CLK-PadR10)") (class "Default")
      (node (ref "U2") (pin "R10") (pinfunction "QSPI_CLK_R10") (pintype "output"))
    )
    (net (code "78") (name "unconnected-(U2A-QSPI_CS-PadP8)") (class "Default")
      (node (ref "U2") (pin "P8") (pinfunction "QSPI_CS_P8") (pintype "output"))
    )
    (net (code "79") (name "unconnected-(U2A-RESERVED-PadR4)") (class "Default")
      (node (ref "U2") (pin "R4") (pinfunction "RESERVED_R4") (pintype "passive+no_connect"))
    )
    (net (code "80") (name "unconnected-(U2A-RESERVED-PadR5)") (class "Default")
      (node (ref "U2") (pin "R5") (pinfunction "RESERVED_R5") (pintype "passive+no_connect"))
    )
    (net (code "81") (name "unconnected-(U2A-RS232_RX-PadN5)") (class "Default")
      (node (ref "U2") (pin "N5") (pinfunction "RS232_RX_N5") (pintype "input+no_connect"))
    )
    (net (code "82") (name "unconnected-(U2A-RS232_TX-PadN6)") (class "Default")
      (node (ref "U2") (pin "N6") (pinfunction "RS232_TX_N6") (pintype "output+no_connect"))
    )
    (net (code "83") (name "unconnected-(U2A-VSENSE-PadC14)") (class "Default")
      (node (ref "U2") (pin "C14") (pinfunction "VSENSE_C14") (pintype "output+no_connect"))
    )
  )
)
